# TubeAmp_power.net
KiCad netlist of a schematic drawn in EAGLE
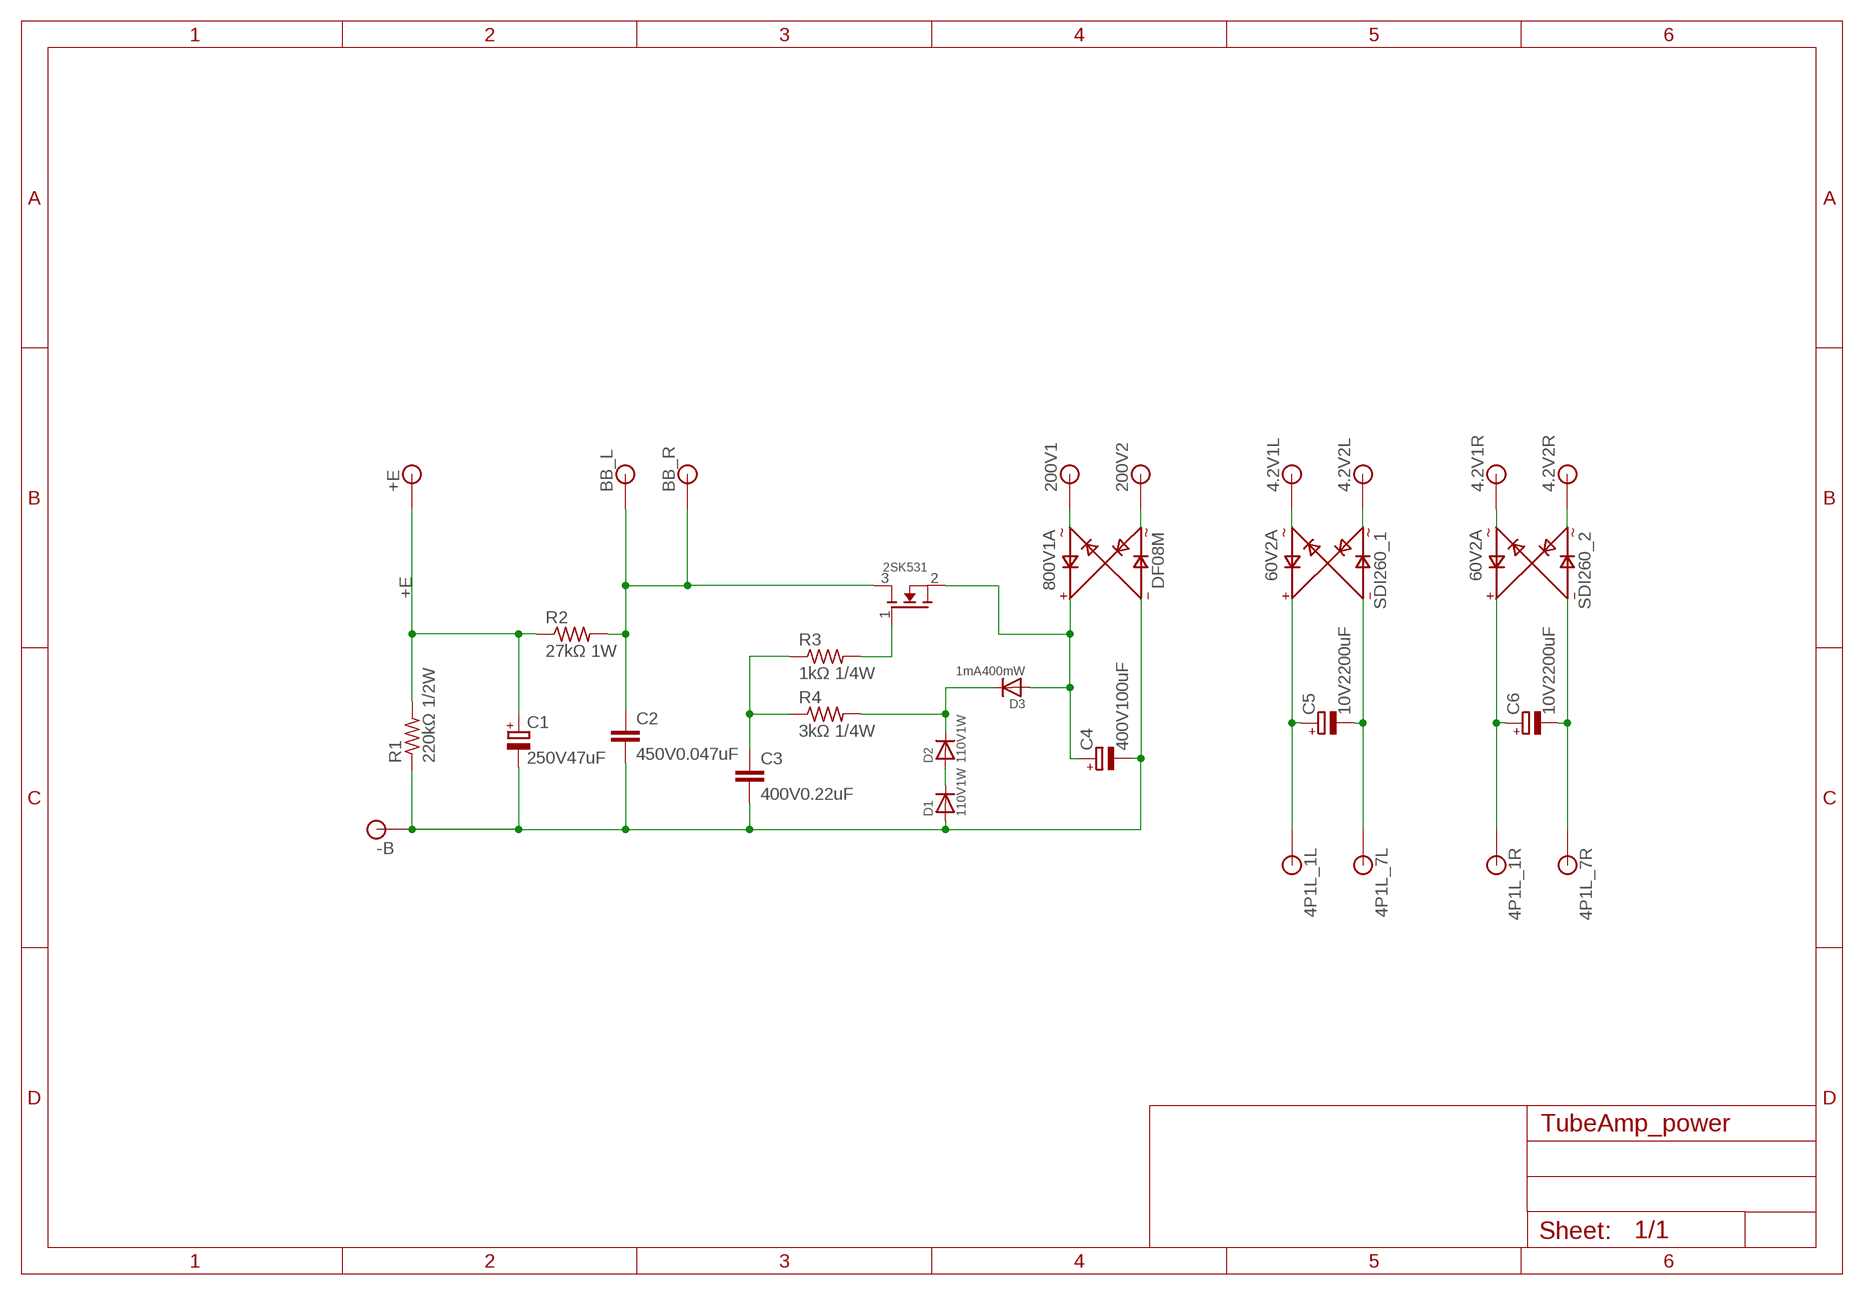
[diagram p0: schematic, sheet 1]

(export (version "E")
  (design (tool "Eeschema 10.0.6"))
  (components
    (comp (ref "+E")
      (value "PIN-1X11.2MM")
      (footprint "eagle-import:PIN-1X1_1.2MM")
      (libsource (lib "eagle-import") (part "PIN-1X11.2MM"))
    )
    (comp (ref "-B")
      (value "PIN-1X11.2MM")
      (footprint "eagle-import:PIN-1X1_1.2MM")
      (libsource (lib "eagle-import") (part "PIN-1X11.2MM"))
    )
    (comp (ref "2SK531")
      (value "MOSFET_N")
      (footprint "eagle-import:MOSFET_N")
      (libsource (lib "eagle-import") (part "MOSFET_N"))
    )
    (comp (ref "4.2V1L")
      (value "PIN-1X11.2MM")
      (footprint "eagle-import:PIN-1X1_1.2MM")
      (libsource (lib "eagle-import") (part "PIN-1X11.2MM"))
    )
    (comp (ref "4.2V1R")
      (value "PIN-1X11.2MM")
      (footprint "eagle-import:PIN-1X1_1.2MM")
      (libsource (lib "eagle-import") (part "PIN-1X11.2MM"))
    )
    (comp (ref "4.2V2L")
      (value "PIN-1X11.2MM")
      (footprint "eagle-import:PIN-1X1_1.2MM")
      (libsource (lib "eagle-import") (part "PIN-1X11.2MM"))
    )
    (comp (ref "4.2V2R")
      (value "PIN-1X11.2MM")
      (footprint "eagle-import:PIN-1X1_1.2MM")
      (libsource (lib "eagle-import") (part "PIN-1X11.2MM"))
    )
    (comp (ref "4P1L_1L")
      (value "PIN-1X11.2MM")
      (footprint "eagle-import:PIN-1X1_1.2MM")
      (libsource (lib "eagle-import") (part "PIN-1X11.2MM"))
    )
    (comp (ref "4P1L_1R")
      (value "PIN-1X11.2MM")
      (footprint "eagle-import:PIN-1X1_1.2MM")
      (libsource (lib "eagle-import") (part "PIN-1X11.2MM"))
    )
    (comp (ref "4P1L_7L")
      (value "PIN-1X11.2MM")
      (footprint "eagle-import:PIN-1X1_1.2MM")
      (libsource (lib "eagle-import") (part "PIN-1X11.2MM"))
    )
    (comp (ref "4P1L_7R")
      (value "PIN-1X11.2MM")
      (footprint "eagle-import:PIN-1X1_1.2MM")
      (libsource (lib "eagle-import") (part "PIN-1X11.2MM"))
    )
    (comp (ref "200V1")
      (value "PIN-1X11.2MM")
      (footprint "eagle-import:PIN-1X1_1.2MM")
      (libsource (lib "eagle-import") (part "PIN-1X11.2MM"))
    )
    (comp (ref "200V2")
      (value "PIN-1X11.2MM")
      (footprint "eagle-import:PIN-1X1_1.2MM")
      (libsource (lib "eagle-import") (part "PIN-1X11.2MM"))
    )
    (comp (ref "BB_L")
      (value "PIN-1X11.2MM")
      (footprint "eagle-import:PIN-1X1_1.2MM")
      (libsource (lib "eagle-import") (part "PIN-1X11.2MM"))
    )
    (comp (ref "BB_R")
      (value "PIN-1X11.2MM")
      (footprint "eagle-import:PIN-1X1_1.2MM")
      (libsource (lib "eagle-import") (part "PIN-1X11.2MM"))
    )
    (comp (ref "C1")
      (value "250V47uF")
      (footprint "eagle-import:CPOL50_90")
      (libsource (lib "eagle-import") (part "CPOL50_90"))
    )
    (comp (ref "C2")
      (value "450V0.047uF")
      (footprint "eagle-import:C150_63X200")
      (libsource (lib "eagle-import") (part "C150_63X200"))
    )
    (comp (ref "C3")
      (value "400V0.22uF")
      (footprint "eagle-import:C100_63X130")
      (libsource (lib "eagle-import") (part "C100_63X130"))
    )
    (comp (ref "C4")
      (value "400V100uF")
      (footprint "eagle-import:CPOL75_150")
      (libsource (lib "eagle-import") (part "CPOL75_150"))
    )
    (comp (ref "C5")
      (value "10V2200uF")
      (footprint "eagle-import:CPOL50_90")
      (libsource (lib "eagle-import") (part "CPOL50_90"))
    )
    (comp (ref "C6")
      (value "10V2200uF")
      (footprint "eagle-import:CPOL50_90")
      (libsource (lib "eagle-import") (part "CPOL50_90"))
    )
    (comp (ref "D1")
      (value "110V1W")
      (footprint "eagle-import:DIODE_63")
      (libsource (lib "eagle-import") (part "DIODE"))
    )
    (comp (ref "D2")
      (value "110V1W")
      (footprint "eagle-import:DIODE_63")
      (libsource (lib "eagle-import") (part "DIODE"))
    )
    (comp (ref "D3")
      (value "1mA400mW")
      (footprint "eagle-import:DIODE_63")
      (libsource (lib "eagle-import") (part "DIODE"))
    )
    (comp (ref "DF08M")
      (value "800V1A")
      (footprint "eagle-import:RECTIFIER")
      (libsource (lib "eagle-import") (part "RECTIFIRE"))
    )
    (comp (ref "R1")
      (value "220kΩ 1/2W")
      (footprint "eagle-import:RESISTOR_1_2W")
      (libsource (lib "eagle-import") (part "RESISTOR1/2W"))
    )
    (comp (ref "R2")
      (value "27kΩ 1W")
      (footprint "eagle-import:RESISTOR_1W")
      (libsource (lib "eagle-import") (part "RESISTOR1W"))
    )
    (comp (ref "R3")
      (value "1kΩ 1/4W")
      (footprint "eagle-import:RESISTOR_1_4W")
      (libsource (lib "eagle-import") (part "RESISTOR1/4W"))
    )
    (comp (ref "R4")
      (value "3kΩ 1/4W")
      (footprint "eagle-import:RESISTOR_1_4W")
      (libsource (lib "eagle-import") (part "RESISTOR1/4W"))
    )
    (comp (ref "SDI260_1")
      (value "60V2A")
      (footprint "eagle-import:RECTIFIER")
      (libsource (lib "eagle-import") (part "RECTIFIRE"))
    )
    (comp (ref "SDI260_2")
      (value "60V2A")
      (footprint "eagle-import:RECTIFIER")
      (libsource (lib "eagle-import") (part "RECTIFIRE"))
    )
  )
  (nets
    (net (code "1") (name "/+E") (class "Default")
      (node (ref "+E") (pin "1") (pinfunction "1_1") (pintype "bidirectional"))
      (node (ref "C1") (pin "+") (pinfunction "+_+") (pintype "passive"))
      (node (ref "R1") (pin "2") (pinfunction "2_2") (pintype "passive"))
      (node (ref "R2") (pin "1") (pinfunction "1_1") (pintype "passive"))
    )
    (net (code "2") (name "Net-(-B-Pad1)") (class "Default")
      (node (ref "-B") (pin "1") (pinfunction "1_1") (pintype "bidirectional"))
      (node (ref "C1") (pin "-") (pinfunction "-_-") (pintype "passive"))
      (node (ref "C2") (pin "2") (pinfunction "2_2") (pintype "passive"))
      (node (ref "C3") (pin "2") (pinfunction "2_2") (pintype "passive"))
      (node (ref "C4") (pin "-") (pinfunction "-_-") (pintype "passive"))
      (node (ref "D1") (pin "A") (pinfunction "A_A") (pintype "passive"))
      (node (ref "DF08M") (pin "-") (pinfunction "-_-") (pintype "passive"))
      (node (ref "R1") (pin "1") (pinfunction "1_1") (pintype "passive"))
    )
    (net (code "3") (name "Net-(2SK531-D)") (class "Default")
      (node (ref "2SK531") (pin "3") (pinfunction "D_3") (pintype "bidirectional"))
      (node (ref "BB_L") (pin "1") (pinfunction "1_1") (pintype "bidirectional"))
      (node (ref "BB_R") (pin "1") (pinfunction "1_1") (pintype "bidirectional"))
      (node (ref "C2") (pin "1") (pinfunction "1_1") (pintype "passive"))
      (node (ref "R2") (pin "2") (pinfunction "2_2") (pintype "passive"))
    )
    (net (code "4") (name "Net-(2SK531-G)") (class "Default")
      (node (ref "2SK531") (pin "1") (pinfunction "G_1") (pintype "bidirectional"))
      (node (ref "R3") (pin "2") (pinfunction "2_2") (pintype "passive"))
    )
    (net (code "5") (name "Net-(2SK531-S)") (class "Default")
      (node (ref "2SK531") (pin "2") (pinfunction "S_2") (pintype "bidirectional"))
      (node (ref "C4") (pin "+") (pinfunction "+_+") (pintype "passive"))
      (node (ref "D3") (pin "A") (pinfunction "A_A") (pintype "passive"))
      (node (ref "DF08M") (pin "+") (pinfunction "+_+") (pintype "passive"))
    )
    (net (code "6") (name "Net-(4.2V1L-Pad1)") (class "Default")
      (node (ref "4.2V1L") (pin "1") (pinfunction "1_1") (pintype "bidirectional"))
      (node (ref "SDI260_1") (pin "AC2") (pinfunction "AC2_AC2") (pintype "passive"))
    )
    (net (code "7") (name "Net-(4.2V1R-Pad1)") (class "Default")
      (node (ref "4.2V1R") (pin "1") (pinfunction "1_1") (pintype "bidirectional"))
      (node (ref "SDI260_2") (pin "AC2") (pinfunction "AC2_AC2") (pintype "passive"))
    )
    (net (code "8") (name "Net-(4.2V2L-Pad1)") (class "Default")
      (node (ref "4.2V2L") (pin "1") (pinfunction "1_1") (pintype "bidirectional"))
      (node (ref "SDI260_1") (pin "AC1") (pinfunction "AC1_AC1") (pintype "passive"))
    )
    (net (code "9") (name "Net-(4.2V2R-Pad1)") (class "Default")
      (node (ref "4.2V2R") (pin "1") (pinfunction "1_1") (pintype "bidirectional"))
      (node (ref "SDI260_2") (pin "AC1") (pinfunction "AC1_AC1") (pintype "passive"))
    )
    (net (code "10") (name "Net-(4P1L_1L-Pad1)") (class "Default")
      (node (ref "4P1L_1L") (pin "1") (pinfunction "1_1") (pintype "bidirectional"))
      (node (ref "C5") (pin "+") (pinfunction "+_+") (pintype "passive"))
      (node (ref "SDI260_1") (pin "+") (pinfunction "+_+") (pintype "passive"))
    )
    (net (code "11") (name "Net-(4P1L_1R-Pad1)") (class "Default")
      (node (ref "4P1L_1R") (pin "1") (pinfunction "1_1") (pintype "bidirectional"))
      (node (ref "C6") (pin "+") (pinfunction "+_+") (pintype "passive"))
      (node (ref "SDI260_2") (pin "+") (pinfunction "+_+") (pintype "passive"))
    )
    (net (code "12") (name "Net-(4P1L_7L-Pad1)") (class "Default")
      (node (ref "4P1L_7L") (pin "1") (pinfunction "1_1") (pintype "bidirectional"))
      (node (ref "C5") (pin "-") (pinfunction "-_-") (pintype "passive"))
      (node (ref "SDI260_1") (pin "-") (pinfunction "-_-") (pintype "passive"))
    )
    (net (code "13") (name "Net-(4P1L_7R-Pad1)") (class "Default")
      (node (ref "4P1L_7R") (pin "1") (pinfunction "1_1") (pintype "bidirectional"))
      (node (ref "C6") (pin "-") (pinfunction "-_-") (pintype "passive"))
      (node (ref "SDI260_2") (pin "-") (pinfunction "-_-") (pintype "passive"))
    )
    (net (code "14") (name "Net-(200V1-Pad1)") (class "Default")
      (node (ref "200V1") (pin "1") (pinfunction "1_1") (pintype "bidirectional"))
      (node (ref "DF08M") (pin "AC2") (pinfunction "AC2_AC2") (pintype "passive"))
    )
    (net (code "15") (name "Net-(200V2-Pad1)") (class "Default")
      (node (ref "200V2") (pin "1") (pinfunction "1_1") (pintype "bidirectional"))
      (node (ref "DF08M") (pin "AC1") (pinfunction "AC1_AC1") (pintype "passive"))
    )
    (net (code "16") (name "Net-(C3-Pad1)") (class "Default")
      (node (ref "C3") (pin "1") (pinfunction "1_1") (pintype "passive"))
      (node (ref "R3") (pin "1") (pinfunction "1_1") (pintype "passive"))
      (node (ref "R4") (pin "1") (pinfunction "1_1") (pintype "passive"))
    )
    (net (code "17") (name "Net-(D1-PadK)") (class "Default")
      (node (ref "D1") (pin "K") (pinfunction "K_K") (pintype "passive"))
      (node (ref "D2") (pin "A") (pinfunction "A_A") (pintype "passive"))
    )
    (net (code "18") (name "Net-(D2-PadK)") (class "Default")
      (node (ref "D2") (pin "K") (pinfunction "K_K") (pintype "passive"))
      (node (ref "D3") (pin "K") (pinfunction "K_K") (pintype "passive"))
      (node (ref "R4") (pin "2") (pinfunction "2_2") (pintype "passive"))
    )
  )
)
